# Motor.net
KiCad netlist of a schematic drawn in EAGLE
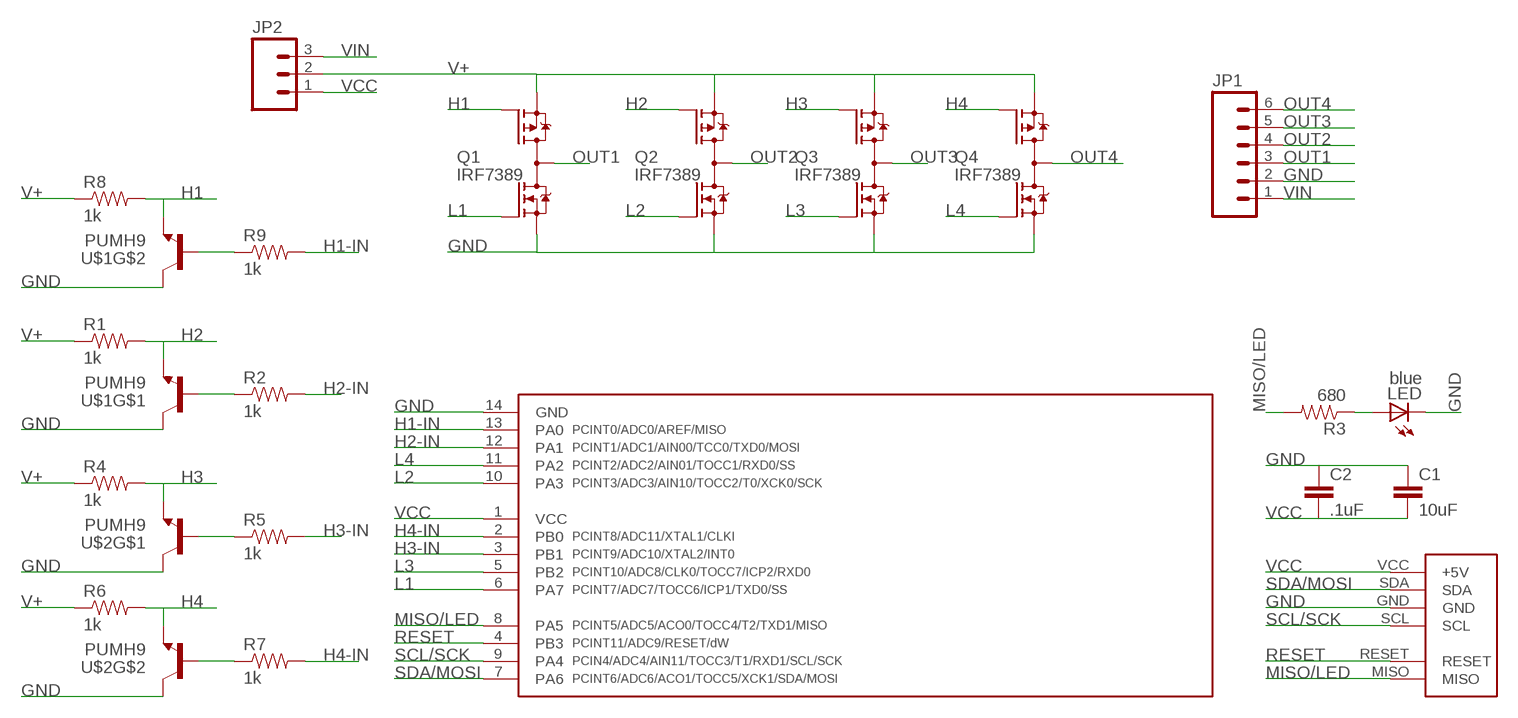
[diagram p0: schematic, sheet 1]

(export (version "E")
  (design (tool "Eeschema 10.0.6"))
  (components
    (comp (ref "C1")
      (value "10uF")
      (footprint "eagle-import:0805")
      (libsource (lib "eagle-import") (part "CAP0805"))
    )
    (comp (ref "C2")
      (value ".1uF")
      (footprint "eagle-import:0805")
      (libsource (lib "eagle-import") (part "CAP0805"))
    )
    (comp (ref "JP1")
      (value "M063.5MM-6")
      (footprint "eagle-import:SCREWTERMINAL-3.5MM-6")
      (libsource (lib "eagle-import") (part "M063.5MM-6"))
    )
    (comp (ref "JP2")
      (value "M03LOCK_NO_SILK")
      (footprint "eagle-import:1X03_LOCK_NO_SILK")
      (libsource (lib "eagle-import") (part "M03LOCK_NO_SILK"))
    )
    (comp (ref "LED")
      (value "blue")
      (footprint "eagle-import:CHIPLED_1206")
      (libsource (lib "eagle-import") (part "LEDCHIPLED_1206"))
    )
    (comp (ref "Q1")
      (value "IRF7389")
      (footprint "eagle-import:SO08-IRF")
      (libsource (lib "eagle-import") (part "IRF7389"))
    )
    (comp (ref "Q2")
      (value "IRF7389")
      (footprint "eagle-import:SO08-IRF")
      (libsource (lib "eagle-import") (part "IRF7389"))
    )
    (comp (ref "Q3")
      (value "IRF7389")
      (footprint "eagle-import:SO08-IRF")
      (libsource (lib "eagle-import") (part "IRF7389"))
    )
    (comp (ref "Q4")
      (value "IRF7389")
      (footprint "eagle-import:SO08-IRF")
      (libsource (lib "eagle-import") (part "IRF7389"))
    )
    (comp (ref "R1")
      (value "1k")
      (footprint "eagle-import:0805")
      (libsource (lib "eagle-import") (part "SparkFun-Resistors_RESISTOR0805-RES"))
    )
    (comp (ref "R2")
      (value "1k")
      (footprint "eagle-import:0805")
      (libsource (lib "eagle-import") (part "SparkFun-Resistors_RESISTOR0805-RES"))
    )
    (comp (ref "R3")
      (value "680")
      (footprint "eagle-import:0805")
      (libsource (lib "eagle-import") (part "RESISTOR0805-RES"))
    )
    (comp (ref "R4")
      (value "1k")
      (footprint "eagle-import:0805")
      (libsource (lib "eagle-import") (part "SparkFun-Resistors_RESISTOR0805-RES"))
    )
    (comp (ref "R5")
      (value "1k")
      (footprint "eagle-import:0805")
      (libsource (lib "eagle-import") (part "SparkFun-Resistors_RESISTOR0805-RES"))
    )
    (comp (ref "R6")
      (value "1k")
      (footprint "eagle-import:0805")
      (libsource (lib "eagle-import") (part "SparkFun-Resistors_RESISTOR0805-RES"))
    )
    (comp (ref "R7")
      (value "1k")
      (footprint "eagle-import:0805")
      (libsource (lib "eagle-import") (part "SparkFun-Resistors_RESISTOR0805-RES"))
    )
    (comp (ref "R8")
      (value "1k")
      (footprint "eagle-import:0805")
      (libsource (lib "eagle-import") (part "SparkFun-Resistors_RESISTOR0805-RES"))
    )
    (comp (ref "R9")
      (value "1k")
      (footprint "eagle-import:0805")
      (libsource (lib "eagle-import") (part "SparkFun-Resistors_RESISTOR0805-RES"))
    )
    (comp (ref "U$1")
      (value "PUMH9")
      (footprint "eagle-import:SOT363")
      (libsource (lib "eagle-import") (part "MMDT3904"))
    )
    (comp (ref "U$2")
      (value "PUMH9")
      (footprint "eagle-import:SOT363")
      (libsource (lib "eagle-import") (part "MMDT3904"))
    )
    (comp (ref "U$3")
      (value "TINY841")
      (footprint "eagle-import:SOIC14")
      (libsource (lib "eagle-import") (part "TINY841"))
    )
    (comp (ref "U$4")
      (value "FOOTPRINTFOOTPRINT-2")
      (footprint "eagle-import:FOOTPRINT2")
      (libsource (lib "eagle-import") (part "FOOTPRINTFOOTPRINT-2"))
    )
  )
  (nets
    (net (code "1") (name "/GND") (class "Default")
      (node (ref "C1") (pin "1") (pinfunction "1_1") (pintype "passive"))
      (node (ref "C2") (pin "1") (pinfunction "1_1") (pintype "passive"))
      (node (ref "JP1") (pin "2") (pinfunction "2_2") (pintype "passive"))
      (node (ref "LED") (pin "C") (pinfunction "C_C") (pintype "passive"))
      (node (ref "Q1") (pin "1") (pinfunction "N-S_1") (pintype "passive"))
      (node (ref "Q2") (pin "1") (pinfunction "N-S_1") (pintype "passive"))
      (node (ref "Q3") (pin "1") (pinfunction "N-S_1") (pintype "passive"))
      (node (ref "Q4") (pin "1") (pinfunction "N-S_1") (pintype "passive"))
      (node (ref "U$1") (pin "3") (pinfunction "C_3") (pintype "passive"))
      (node (ref "U$1") (pin "6") (pinfunction "C_6") (pintype "passive"))
      (node (ref "U$2") (pin "3") (pinfunction "C_3") (pintype "passive"))
      (node (ref "U$2") (pin "6") (pinfunction "C_6") (pintype "passive"))
      (node (ref "U$3") (pin "14") (pinfunction "GND_14") (pintype "bidirectional"))
      (node (ref "U$4") (pin "GND") (pinfunction "GND_GND") (pintype "power_in"))
    )
    (net (code "2") (name "/H1") (class "Default")
      (node (ref "Q1") (pin "4") (pinfunction "P-G_4") (pintype "passive"))
      (node (ref "R8") (pin "2") (pinfunction "2_2") (pintype "passive"))
      (node (ref "U$1") (pin "1") (pinfunction "E_1") (pintype "passive"))
    )
    (net (code "3") (name "/H1-IN") (class "Default")
      (node (ref "R9") (pin "2") (pinfunction "2_2") (pintype "passive"))
      (node (ref "U$3") (pin "13") (pinfunction "PA0_13") (pintype "bidirectional"))
    )
    (net (code "4") (name "/H2") (class "Default")
      (node (ref "Q2") (pin "4") (pinfunction "P-G_4") (pintype "passive"))
      (node (ref "R1") (pin "2") (pinfunction "2_2") (pintype "passive"))
      (node (ref "U$1") (pin "4") (pinfunction "E_4") (pintype "passive"))
    )
    (net (code "5") (name "/H2-IN") (class "Default")
      (node (ref "R2") (pin "2") (pinfunction "2_2") (pintype "passive"))
      (node (ref "U$3") (pin "12") (pinfunction "PA1_12") (pintype "bidirectional"))
    )
    (net (code "6") (name "/H3") (class "Default")
      (node (ref "Q3") (pin "4") (pinfunction "P-G_4") (pintype "passive"))
      (node (ref "R4") (pin "2") (pinfunction "2_2") (pintype "passive"))
      (node (ref "U$2") (pin "4") (pinfunction "E_4") (pintype "passive"))
    )
    (net (code "7") (name "/H3-IN") (class "Default")
      (node (ref "R5") (pin "2") (pinfunction "2_2") (pintype "passive"))
      (node (ref "U$3") (pin "3") (pinfunction "PB1_3") (pintype "bidirectional"))
    )
    (net (code "8") (name "/H4") (class "Default")
      (node (ref "Q4") (pin "4") (pinfunction "P-G_4") (pintype "passive"))
      (node (ref "R6") (pin "2") (pinfunction "2_2") (pintype "passive"))
      (node (ref "U$2") (pin "1") (pinfunction "E_1") (pintype "passive"))
    )
    (net (code "9") (name "/H4-IN") (class "Default")
      (node (ref "R7") (pin "2") (pinfunction "2_2") (pintype "passive"))
      (node (ref "U$3") (pin "2") (pinfunction "PB0_2") (pintype "bidirectional"))
    )
    (net (code "10") (name "/L1") (class "Default")
      (node (ref "Q1") (pin "2") (pinfunction "N-G_2") (pintype "passive"))
      (node (ref "U$3") (pin "6") (pinfunction "PA7_6") (pintype "bidirectional"))
    )
    (net (code "11") (name "/L2") (class "Default")
      (node (ref "Q2") (pin "2") (pinfunction "N-G_2") (pintype "passive"))
      (node (ref "U$3") (pin "10") (pinfunction "PA3_10") (pintype "bidirectional"))
    )
    (net (code "12") (name "/L3") (class "Default")
      (node (ref "Q3") (pin "2") (pinfunction "N-G_2") (pintype "passive"))
      (node (ref "U$3") (pin "5") (pinfunction "PB2_5") (pintype "bidirectional"))
    )
    (net (code "13") (name "/L4") (class "Default")
      (node (ref "Q4") (pin "2") (pinfunction "N-G_2") (pintype "passive"))
      (node (ref "U$3") (pin "11") (pinfunction "PA2_11") (pintype "bidirectional"))
    )
    (net (code "14") (name "/MISO{slash}LED") (class "Default")
      (node (ref "R3") (pin "2") (pinfunction "2_2") (pintype "passive"))
      (node (ref "U$3") (pin "8") (pinfunction "PA5_8") (pintype "bidirectional"))
      (node (ref "U$4") (pin "MISO") (pinfunction "MISO_MISO") (pintype "bidirectional"))
    )
    (net (code "15") (name "/OUT1") (class "Default")
      (node (ref "JP1") (pin "3") (pinfunction "3_3") (pintype "passive"))
      (node (ref "Q1") (pin "5") (pinfunction "D_5") (pintype "passive"))
      (node (ref "Q1") (pin "6") (pinfunction "D_6") (pintype "passive"))
      (node (ref "Q1") (pin "7") (pinfunction "D_7") (pintype "passive"))
      (node (ref "Q1") (pin "8") (pinfunction "D_8") (pintype "passive"))
    )
    (net (code "16") (name "/OUT2") (class "Default")
      (node (ref "JP1") (pin "4") (pinfunction "4_4") (pintype "passive"))
      (node (ref "Q2") (pin "5") (pinfunction "D_5") (pintype "passive"))
      (node (ref "Q2") (pin "6") (pinfunction "D_6") (pintype "passive"))
      (node (ref "Q2") (pin "7") (pinfunction "D_7") (pintype "passive"))
      (node (ref "Q2") (pin "8") (pinfunction "D_8") (pintype "passive"))
    )
    (net (code "17") (name "/OUT3") (class "Default")
      (node (ref "JP1") (pin "5") (pinfunction "5_5") (pintype "passive"))
      (node (ref "Q3") (pin "5") (pinfunction "D_5") (pintype "passive"))
      (node (ref "Q3") (pin "6") (pinfunction "D_6") (pintype "passive"))
      (node (ref "Q3") (pin "7") (pinfunction "D_7") (pintype "passive"))
      (node (ref "Q3") (pin "8") (pinfunction "D_8") (pintype "passive"))
    )
    (net (code "18") (name "/OUT4") (class "Default")
      (node (ref "JP1") (pin "6") (pinfunction "6_6") (pintype "passive"))
      (node (ref "Q4") (pin "5") (pinfunction "D_5") (pintype "passive"))
      (node (ref "Q4") (pin "6") (pinfunction "D_6") (pintype "passive"))
      (node (ref "Q4") (pin "7") (pinfunction "D_7") (pintype "passive"))
      (node (ref "Q4") (pin "8") (pinfunction "D_8") (pintype "passive"))
    )
    (net (code "19") (name "/RESET") (class "Default")
      (node (ref "U$3") (pin "4") (pinfunction "PB3_4") (pintype "bidirectional"))
      (node (ref "U$4") (pin "RESET") (pinfunction "RESET_RESET") (pintype "bidirectional"))
    )
    (net (code "20") (name "/SCL{slash}SCK") (class "Default")
      (node (ref "U$3") (pin "9") (pinfunction "PA4_9") (pintype "bidirectional"))
      (node (ref "U$4") (pin "SCL") (pinfunction "SCL_SCL") (pintype "bidirectional"))
    )
    (net (code "21") (name "/SDA{slash}MOSI") (class "Default")
      (node (ref "U$3") (pin "7") (pinfunction "PA6_7") (pintype "bidirectional"))
      (node (ref "U$4") (pin "SDA") (pinfunction "SDA_SDA") (pintype "bidirectional"))
    )
    (net (code "22") (name "/V+") (class "Default")
      (node (ref "JP2") (pin "2") (pinfunction "2_2") (pintype "passive"))
      (node (ref "Q1") (pin "3") (pinfunction "P-S_3") (pintype "passive"))
      (node (ref "Q2") (pin "3") (pinfunction "P-S_3") (pintype "passive"))
      (node (ref "Q3") (pin "3") (pinfunction "P-S_3") (pintype "passive"))
      (node (ref "Q4") (pin "3") (pinfunction "P-S_3") (pintype "passive"))
      (node (ref "R1") (pin "1") (pinfunction "1_1") (pintype "passive"))
      (node (ref "R4") (pin "1") (pinfunction "1_1") (pintype "passive"))
      (node (ref "R6") (pin "1") (pinfunction "1_1") (pintype "passive"))
      (node (ref "R8") (pin "1") (pinfunction "1_1") (pintype "passive"))
    )
    (net (code "23") (name "/VCC") (class "Default")
      (node (ref "C1") (pin "2") (pinfunction "2_2") (pintype "passive"))
      (node (ref "C2") (pin "2") (pinfunction "2_2") (pintype "passive"))
      (node (ref "JP2") (pin "1") (pinfunction "1_1") (pintype "passive"))
      (node (ref "U$3") (pin "1") (pinfunction "VCC_1") (pintype "bidirectional"))
      (node (ref "U$4") (pin "VCC") (pinfunction "+5V_VCC") (pintype "power_in"))
    )
    (net (code "24") (name "/VIN") (class "Default")
      (node (ref "JP1") (pin "1") (pinfunction "1_1") (pintype "passive"))
      (node (ref "JP2") (pin "3") (pinfunction "3_3") (pintype "passive"))
    )
    (net (code "25") (name "Net-(LED-PadA)") (class "Default")
      (node (ref "LED") (pin "A") (pinfunction "A_A") (pintype "passive"))
      (node (ref "R3") (pin "1") (pinfunction "1_1") (pintype "passive"))
    )
    (net (code "26") (name "Net-(U$1A-B)") (class "Default")
      (node (ref "R2") (pin "1") (pinfunction "1_1") (pintype "passive"))
      (node (ref "U$1") (pin "5") (pinfunction "B_5") (pintype "passive"))
    )
    (net (code "27") (name "Net-(U$1B-B)") (class "Default")
      (node (ref "R9") (pin "1") (pinfunction "1_1") (pintype "passive"))
      (node (ref "U$1") (pin "2") (pinfunction "B_2") (pintype "passive"))
    )
    (net (code "28") (name "Net-(U$2A-B)") (class "Default")
      (node (ref "R5") (pin "1") (pinfunction "1_1") (pintype "passive"))
      (node (ref "U$2") (pin "5") (pinfunction "B_5") (pintype "passive"))
    )
    (net (code "29") (name "Net-(U$2B-B)") (class "Default")
      (node (ref "R7") (pin "1") (pinfunction "1_1") (pintype "passive"))
      (node (ref "U$2") (pin "2") (pinfunction "B_2") (pintype "passive"))
    )
  )
)
